# Kite-ARM-STM32F103.net
KiCad netlist of a schematic drawn in EAGLE
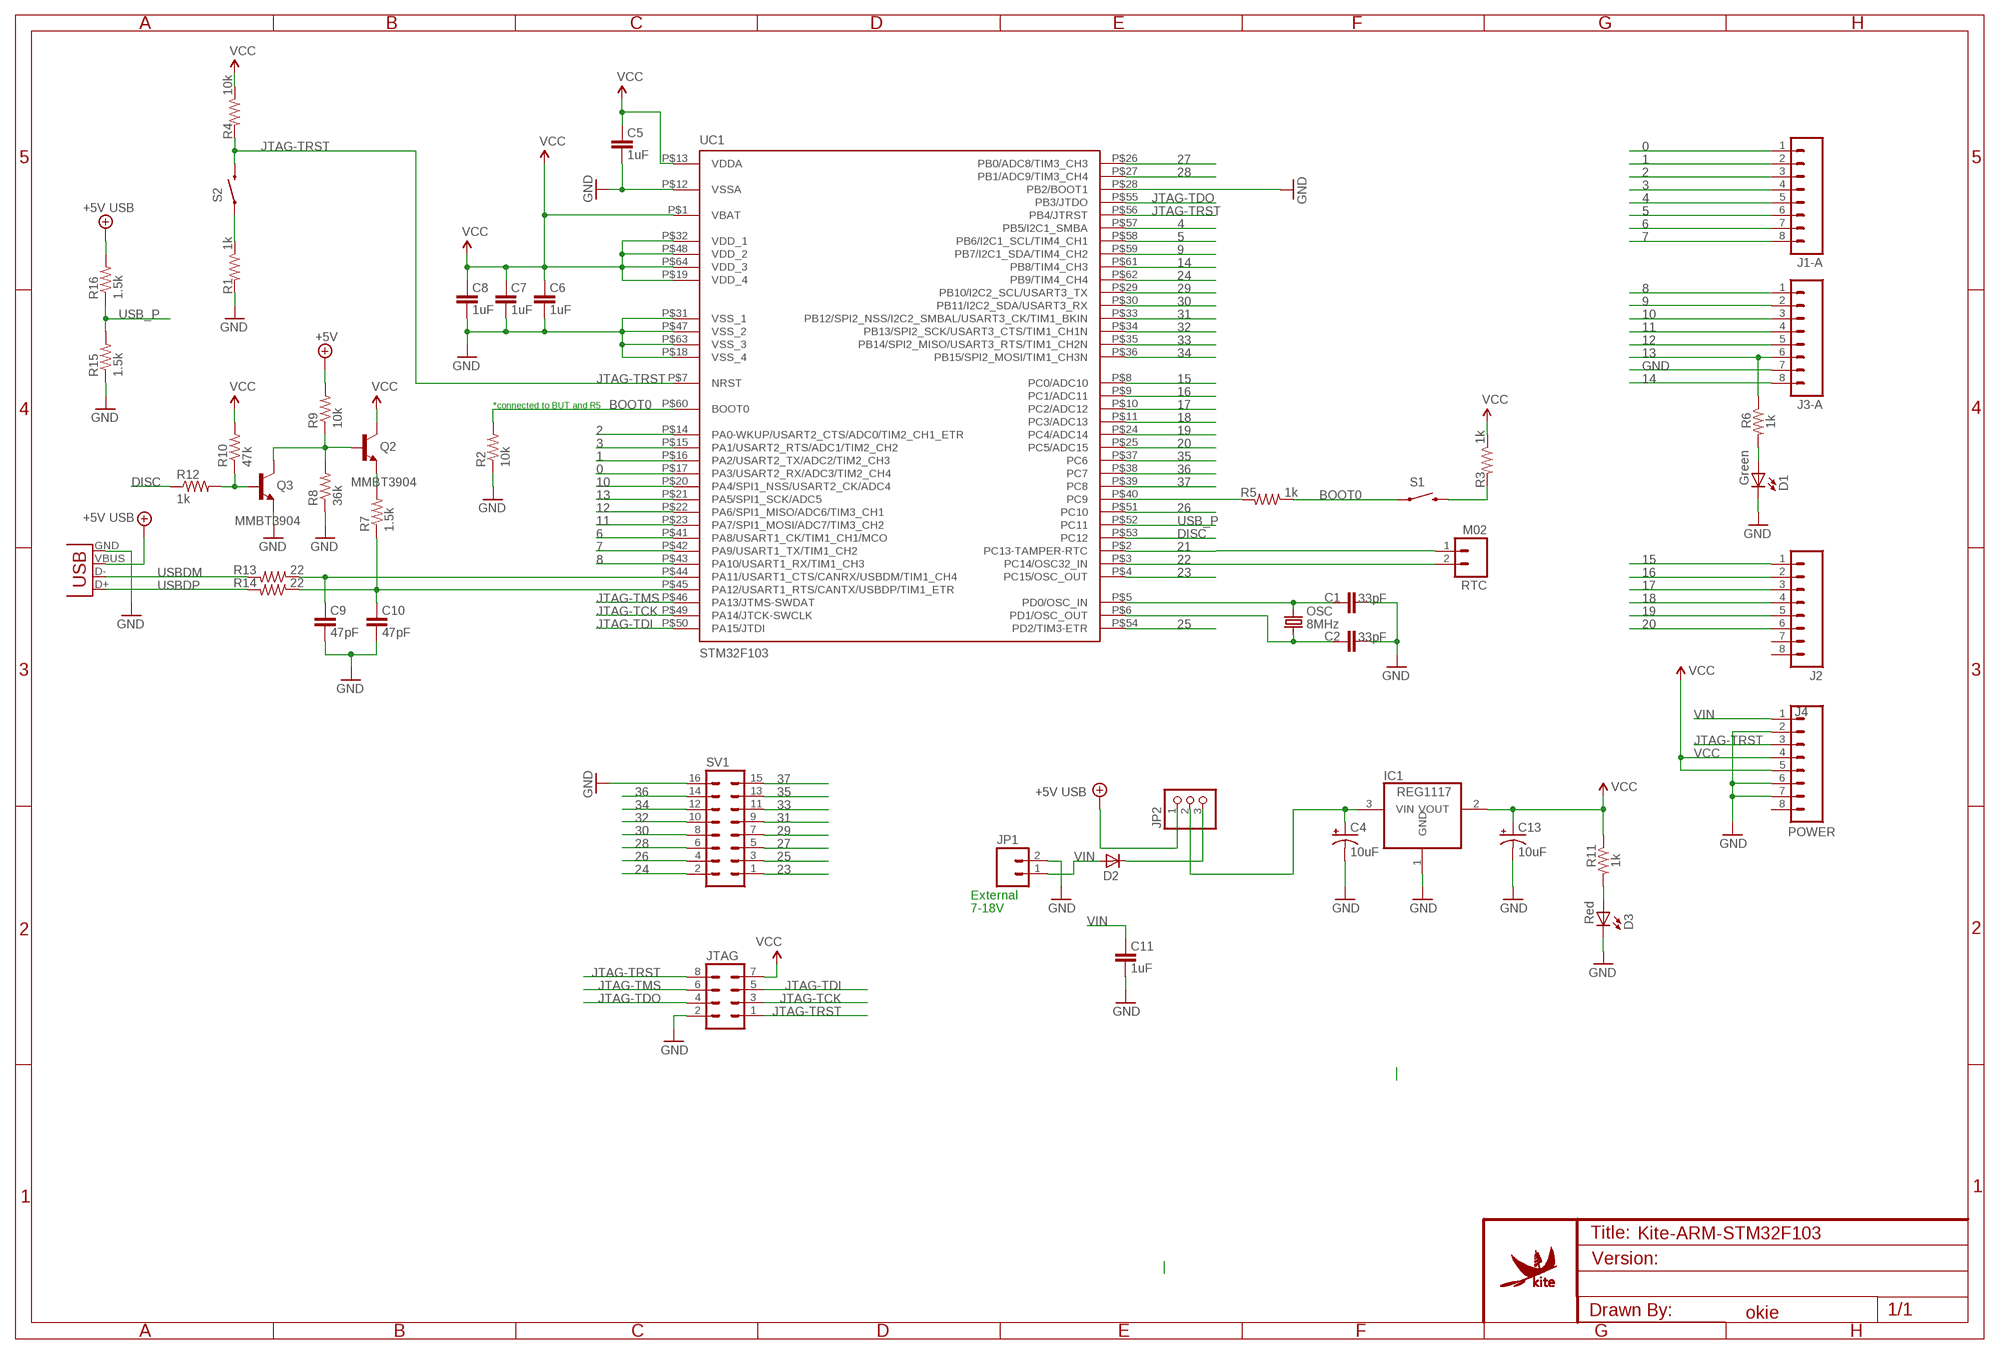
[diagram p0: schematic, sheet 1]

(export (version "E")
  (design (tool "Eeschema 10.0.6"))
  (components
    (comp (ref "C1")
      (value "33pF")
      (footprint "eagle-import:0603")
      (libsource (lib "eagle-import") (part "CAP0603"))
    )
    (comp (ref "C2")
      (value "33pF")
      (footprint "eagle-import:0603")
      (libsource (lib "eagle-import") (part "CAP0603"))
    )
    (comp (ref "C4")
      (value "10uF")
      (footprint "eagle-import:EIA3216")
      (libsource (lib "eagle-import") (part "10UF-TANT"))
    )
    (comp (ref "C5")
      (value "1uF")
      (footprint "eagle-import:0603")
      (libsource (lib "eagle-import") (part "CAP0603"))
    )
    (comp (ref "C6")
      (value "1uF")
      (footprint "eagle-import:0603")
      (libsource (lib "eagle-import") (part "CAP0603"))
    )
    (comp (ref "C7")
      (value "1uF")
      (footprint "eagle-import:0603")
      (libsource (lib "eagle-import") (part "CAP0603"))
    )
    (comp (ref "C8")
      (value "1uF")
      (footprint "eagle-import:0603")
      (libsource (lib "eagle-import") (part "CAP0603"))
    )
    (comp (ref "C9")
      (value "47pF")
      (footprint "eagle-import:0603")
      (libsource (lib "eagle-import") (part "CAP0603"))
    )
    (comp (ref "C10")
      (value "47pF")
      (footprint "eagle-import:0603")
      (libsource (lib "eagle-import") (part "CAP0603"))
    )
    (comp (ref "C11")
      (value "1uF")
      (footprint "eagle-import:0603")
      (libsource (lib "eagle-import") (part "CAP0603"))
    )
    (comp (ref "C13")
      (value "10uF")
      (footprint "eagle-import:EIA3216")
      (libsource (lib "eagle-import") (part "10UF-TANT"))
    )
    (comp (ref "D1")
      (value "Green")
      (footprint "eagle-import:LED-0603")
      (libsource (lib "eagle-import") (part "LED0603"))
    )
    (comp (ref "D2")
      (value "DIODESMA")
      (footprint "eagle-import:SMA-DIODE")
      (libsource (lib "eagle-import") (part "DIODESMA"))
    )
    (comp (ref "D3")
      (value "Red")
      (footprint "eagle-import:LED-0603")
      (libsource (lib "eagle-import") (part "LED0603"))
    )
    (comp (ref "IC1")
      (value "REG1117")
      (footprint "eagle-import:SOT223")
      (libsource (lib "eagle-import") (part "REG1117"))
    )
    (comp (ref "J1-A")
      (value "M081X08")
      (footprint "eagle-import:1X08")
      (libsource (lib "eagle-import") (part "M081X08"))
    )
    (comp (ref "J2")
      (value "M081X08")
      (footprint "eagle-import:1X08")
      (libsource (lib "eagle-import") (part "M081X08"))
    )
    (comp (ref "J3-A")
      (value "M081X08")
      (footprint "eagle-import:1X08")
      (libsource (lib "eagle-import") (part "M081X08"))
    )
    (comp (ref "J4")
      (value "POWER")
      (footprint "eagle-import:1X08")
      (libsource (lib "eagle-import") (part "M081X08"))
    )
    (comp (ref "JP1")
      (value "M02POLAR")
      (footprint "eagle-import:MOLEX-1X2")
      (libsource (lib "eagle-import") (part "M02POLAR"))
    )
    (comp (ref "JP2")
      (value "PINHD-1X3")
      (footprint "eagle-import:1X03")
      (libsource (lib "eagle-import") (part "PINHD-1X3"))
    )
    (comp (ref "JTAG")
      (value "MA04-2")
      (footprint "eagle-import:MA04-2")
      (libsource (lib "eagle-import") (part "MA04-2"))
    )
    (comp (ref "OSC")
      (value "8MHz")
      (footprint "eagle-import:CRYSTAL-SMD-5X3")
      (libsource (lib "eagle-import") (part "CRYSTAL5X3"))
    )
    (comp (ref "Q2")
      (value "MMBT3904")
      (footprint "eagle-import:SOT23")
      (libsource (lib "eagle-import") (part "TRANSISTOR_NPNSOT23"))
    )
    (comp (ref "Q3")
      (value "MMBT3904")
      (footprint "eagle-import:SOT23")
      (libsource (lib "eagle-import") (part "TRANSISTOR_NPNSOT23"))
    )
    (comp (ref "R1")
      (value "1k")
      (footprint "eagle-import:0603")
      (libsource (lib "eagle-import") (part "RESISTOR0603"))
    )
    (comp (ref "R2")
      (value "10k")
      (footprint "eagle-import:0603")
      (libsource (lib "eagle-import") (part "RESISTOR0603"))
    )
    (comp (ref "R3")
      (value "1k")
      (footprint "eagle-import:0603")
      (libsource (lib "eagle-import") (part "RESISTOR0603"))
    )
    (comp (ref "R4")
      (value "10k")
      (footprint "eagle-import:0603")
      (libsource (lib "eagle-import") (part "RESISTOR0603"))
    )
    (comp (ref "R5")
      (value "1k")
      (footprint "eagle-import:0603")
      (libsource (lib "eagle-import") (part "RESISTOR0603"))
    )
    (comp (ref "R6")
      (value "1k")
      (footprint "eagle-import:0603")
      (libsource (lib "eagle-import") (part "RESISTOR0603"))
    )
    (comp (ref "R7")
      (value "1.5k")
      (footprint "eagle-import:0603")
      (libsource (lib "eagle-import") (part "RESISTOR0603"))
    )
    (comp (ref "R8")
      (value "36k")
      (footprint "eagle-import:0603")
      (libsource (lib "eagle-import") (part "RESISTOR0603"))
    )
    (comp (ref "R9")
      (value "10k")
      (footprint "eagle-import:0603")
      (libsource (lib "eagle-import") (part "RESISTOR0603"))
    )
    (comp (ref "R10")
      (value "47k")
      (footprint "eagle-import:0603")
      (libsource (lib "eagle-import") (part "RESISTOR0603"))
    )
    (comp (ref "R11")
      (value "1k")
      (footprint "eagle-import:0603")
      (libsource (lib "eagle-import") (part "RESISTOR0603"))
    )
    (comp (ref "R12")
      (value "1k")
      (footprint "eagle-import:0603")
      (libsource (lib "eagle-import") (part "RESISTOR0603"))
    )
    (comp (ref "R13")
      (value "22")
      (footprint "eagle-import:0603")
      (libsource (lib "eagle-import") (part "RESISTOR0603"))
    )
    (comp (ref "R14")
      (value "22")
      (footprint "eagle-import:0603")
      (libsource (lib "eagle-import") (part "RESISTOR0603"))
    )
    (comp (ref "R15")
      (value "1.5k")
      (footprint "eagle-import:0603")
      (libsource (lib "eagle-import") (part "RESISTOR0603"))
    )
    (comp (ref "R16")
      (value "1.5k")
      (footprint "eagle-import:0603")
      (libsource (lib "eagle-import") (part "RESISTOR0603"))
    )
    (comp (ref "RTC")
      (value "M02")
      (footprint "eagle-import:1X02")
      (libsource (lib "eagle-import") (part "M02NG"))
    )
    (comp (ref "S1")
      (value "SWITCH-MOMENTARY-2-SMD-1101NE")
      (footprint "eagle-import:TACTILE-SWITCH-1101NE")
      (libsource (lib "eagle-import") (part "SWITCH-MOMENTARY-2-SMD-1101NE"))
    )
    (comp (ref "S2")
      (value "SWITCH-MOMENTARY-2-SMD-1101NE")
      (footprint "eagle-import:TACTILE-SWITCH-1101NE")
      (libsource (lib "eagle-import") (part "SWITCH-MOMENTARY-2-SMD-1101NE"))
    )
    (comp (ref "SV1")
      (value "MA08-2")
      (footprint "eagle-import:MA08-2")
      (libsource (lib "eagle-import") (part "MA08-2"))
    )
    (comp (ref "U$3")
      (value "KITE-LOGO-STM32-MEDIUM")
      (footprint "eagle-import:KITE-STM32-LOGO-MEDIUM")
      (libsource (lib "eagle-import") (part "KITE-LOGO-STM32-MEDIUM"))
    )
    (comp (ref "UC1")
      (value "STM32F103")
      (footprint "eagle-import:TQFP-10X10-64")
      (libsource (lib "eagle-import") (part "STM32F103"))
    )
    (comp (ref "X1")
      (value "USBSMD")
      (footprint "eagle-import:USB-MINIB")
      (libsource (lib "eagle-import") (part "USBSMD"))
    )
  )
  (nets
    (net (code "1") (name "+5V") (class "Default")
      (node (ref "JP2") (pin "1") (pinfunction "1_1") (pintype "passive"))
      (node (ref "R16") (pin "2") (pinfunction "2_2") (pintype "passive"))
      (node (ref "R9") (pin "2") (pinfunction "2_2") (pintype "passive"))
      (node (ref "X1") (pin "VBUS") (pinfunction "VBUS_VBUS") (pintype "bidirectional"))
    )
    (net (code "2") (name "/0") (class "Default")
      (node (ref "J1-A") (pin "1") (pinfunction "1_1") (pintype "passive"))
      (node (ref "UC1") (pin "P$17") (pinfunction "PA3/USART2_RX/ADC3/TIM2_CH4_P$17") (pintype "bidirectional"))
    )
    (net (code "3") (name "/1") (class "Default")
      (node (ref "J1-A") (pin "2") (pinfunction "2_2") (pintype "passive"))
      (node (ref "UC1") (pin "P$16") (pinfunction "PA2/USART2_TX/ADC2/TIM2_CH3_P$16") (pintype "bidirectional"))
    )
    (net (code "4") (name "/2") (class "Default")
      (node (ref "J1-A") (pin "3") (pinfunction "3_3") (pintype "passive"))
      (node (ref "UC1") (pin "P$14") (pinfunction "PA0-WKUP/USART2_CTS/ADC0/TIM2_CH1_ETR_P$14") (pintype "bidirectional"))
    )
    (net (code "5") (name "/3") (class "Default")
      (node (ref "J1-A") (pin "4") (pinfunction "4_4") (pintype "passive"))
      (node (ref "UC1") (pin "P$15") (pinfunction "PA1/USART2_RTS/ADC1/TIM2_CH2_P$15") (pintype "bidirectional"))
    )
    (net (code "6") (name "/4") (class "Default")
      (node (ref "J1-A") (pin "5") (pinfunction "5_5") (pintype "passive"))
      (node (ref "UC1") (pin "P$57") (pinfunction "PB5/I2C1_SMBA_P$57") (pintype "bidirectional"))
    )
    (net (code "7") (name "/5") (class "Default")
      (node (ref "J1-A") (pin "6") (pinfunction "6_6") (pintype "passive"))
      (node (ref "UC1") (pin "P$58") (pinfunction "PB6/I2C1_SCL/TIM4_CH1_P$58") (pintype "bidirectional"))
    )
    (net (code "8") (name "/6") (class "Default")
      (node (ref "J1-A") (pin "7") (pinfunction "7_7") (pintype "passive"))
      (node (ref "UC1") (pin "P$41") (pinfunction "PA8/USART1_CK/TIM1_CH1/MCO_P$41") (pintype "bidirectional"))
    )
    (net (code "9") (name "/7") (class "Default")
      (node (ref "J1-A") (pin "8") (pinfunction "8_8") (pintype "passive"))
      (node (ref "UC1") (pin "P$42") (pinfunction "PA9/USART1_TX/TIM1_CH2_P$42") (pintype "bidirectional"))
    )
    (net (code "10") (name "/8") (class "Default")
      (node (ref "J3-A") (pin "1") (pinfunction "1_1") (pintype "passive"))
      (node (ref "UC1") (pin "P$43") (pinfunction "PA10/USART1_RX/TIM1_CH3_P$43") (pintype "bidirectional"))
    )
    (net (code "11") (name "/9") (class "Default")
      (node (ref "J3-A") (pin "2") (pinfunction "2_2") (pintype "passive"))
      (node (ref "UC1") (pin "P$59") (pinfunction "PB7/I2C1_SDA/TIM4_CH2_P$59") (pintype "bidirectional"))
    )
    (net (code "12") (name "/10") (class "Default")
      (node (ref "J3-A") (pin "3") (pinfunction "3_3") (pintype "passive"))
      (node (ref "UC1") (pin "P$20") (pinfunction "PA4/SPI1_NSS/USART2_CK/ADC4_P$20") (pintype "bidirectional"))
    )
    (net (code "13") (name "/11") (class "Default")
      (node (ref "J3-A") (pin "4") (pinfunction "4_4") (pintype "passive"))
      (node (ref "UC1") (pin "P$23") (pinfunction "PA7/SPI1_MOSI/ADC7/TIM3_CH2_P$23") (pintype "bidirectional"))
    )
    (net (code "14") (name "/12") (class "Default")
      (node (ref "J3-A") (pin "5") (pinfunction "5_5") (pintype "passive"))
      (node (ref "UC1") (pin "P$22") (pinfunction "PA6/SPI1_MISO/ADC6/TIM3_CH1_P$22") (pintype "bidirectional"))
    )
    (net (code "15") (name "/13") (class "Default")
      (node (ref "J3-A") (pin "6") (pinfunction "6_6") (pintype "passive"))
      (node (ref "R6") (pin "1") (pinfunction "1_1") (pintype "passive"))
      (node (ref "UC1") (pin "P$21") (pinfunction "PA5/SPI1_SCK/ADC5_P$21") (pintype "bidirectional"))
    )
    (net (code "16") (name "/14") (class "Default")
      (node (ref "J3-A") (pin "8") (pinfunction "8_8") (pintype "passive"))
      (node (ref "UC1") (pin "P$61") (pinfunction "PB8/TIM4_CH3_P$61") (pintype "bidirectional"))
    )
    (net (code "17") (name "/15") (class "Default")
      (node (ref "J2") (pin "1") (pinfunction "1_1") (pintype "passive"))
      (node (ref "UC1") (pin "P$8") (pinfunction "PC0/ADC10_P$8") (pintype "bidirectional"))
    )
    (net (code "18") (name "/16") (class "Default")
      (node (ref "J2") (pin "2") (pinfunction "2_2") (pintype "passive"))
      (node (ref "UC1") (pin "P$9") (pinfunction "PC1/ADC11_P$9") (pintype "bidirectional"))
    )
    (net (code "19") (name "/17") (class "Default")
      (node (ref "J2") (pin "3") (pinfunction "3_3") (pintype "passive"))
      (node (ref "UC1") (pin "P$10") (pinfunction "PC2/ADC12_P$10") (pintype "bidirectional"))
    )
    (net (code "20") (name "/18") (class "Default")
      (node (ref "J2") (pin "4") (pinfunction "4_4") (pintype "passive"))
      (node (ref "UC1") (pin "P$11") (pinfunction "PC3/ADC13_P$11") (pintype "bidirectional"))
    )
    (net (code "21") (name "/19") (class "Default")
      (node (ref "J2") (pin "5") (pinfunction "5_5") (pintype "passive"))
      (node (ref "UC1") (pin "P$24") (pinfunction "PC4/ADC14_P$24") (pintype "bidirectional"))
    )
    (net (code "22") (name "/20") (class "Default")
      (node (ref "J2") (pin "6") (pinfunction "6_6") (pintype "passive"))
      (node (ref "UC1") (pin "P$25") (pinfunction "PC5/ADC15_P$25") (pintype "bidirectional"))
    )
    (net (code "23") (name "/21") (class "Default")
      (node (ref "RTC") (pin "1") (pinfunction "1_1") (pintype "passive"))
      (node (ref "UC1") (pin "P$2") (pinfunction "PC13-TAMPER-RTC_P$2") (pintype "bidirectional"))
    )
    (net (code "24") (name "/22") (class "Default")
      (node (ref "RTC") (pin "2") (pinfunction "2_2") (pintype "passive"))
      (node (ref "UC1") (pin "P$3") (pinfunction "PC14/OSC32_IN_P$3") (pintype "bidirectional"))
    )
    (net (code "25") (name "/23") (class "Default")
      (node (ref "SV1") (pin "1") (pinfunction "1_1") (pintype "passive"))
      (node (ref "UC1") (pin "P$4") (pinfunction "PC15/OSC_OUT_P$4") (pintype "bidirectional"))
    )
    (net (code "26") (name "/24") (class "Default")
      (node (ref "SV1") (pin "2") (pinfunction "2_2") (pintype "passive"))
      (node (ref "UC1") (pin "P$62") (pinfunction "PB9/TIM4_CH4_P$62") (pintype "bidirectional"))
    )
    (net (code "27") (name "/25") (class "Default")
      (node (ref "SV1") (pin "3") (pinfunction "3_3") (pintype "passive"))
      (node (ref "UC1") (pin "P$54") (pinfunction "PD2/TIM3-ETR_P$54") (pintype "bidirectional"))
    )
    (net (code "28") (name "/26") (class "Default")
      (node (ref "SV1") (pin "4") (pinfunction "4_4") (pintype "passive"))
      (node (ref "UC1") (pin "P$51") (pinfunction "PC10_P$51") (pintype "bidirectional"))
    )
    (net (code "29") (name "/27") (class "Default")
      (node (ref "SV1") (pin "5") (pinfunction "5_5") (pintype "passive"))
      (node (ref "UC1") (pin "P$26") (pinfunction "PB0/ADC8/TIM3_CH3_P$26") (pintype "bidirectional"))
    )
    (net (code "30") (name "/28") (class "Default")
      (node (ref "SV1") (pin "6") (pinfunction "6_6") (pintype "passive"))
      (node (ref "UC1") (pin "P$27") (pinfunction "PB1/ADC9/TIM3_CH4_P$27") (pintype "bidirectional"))
    )
    (net (code "31") (name "/29") (class "Default")
      (node (ref "SV1") (pin "7") (pinfunction "7_7") (pintype "passive"))
      (node (ref "UC1") (pin "P$29") (pinfunction "PB10/I2C2_SCL/USART3_TX_P$29") (pintype "bidirectional"))
    )
    (net (code "32") (name "/30") (class "Default")
      (node (ref "SV1") (pin "8") (pinfunction "8_8") (pintype "passive"))
      (node (ref "UC1") (pin "P$30") (pinfunction "PB11/I2C2_SDA/USART3_RX_P$30") (pintype "bidirectional"))
    )
    (net (code "33") (name "/31") (class "Default")
      (node (ref "SV1") (pin "9") (pinfunction "9_9") (pintype "passive"))
      (node (ref "UC1") (pin "P$33") (pinfunction "PB12/SPI2_NSS/I2C2_SMBAL/USART3_CK/TIM1_BKIN_P$33") (pintype "bidirectional"))
    )
    (net (code "34") (name "/32") (class "Default")
      (node (ref "SV1") (pin "10") (pinfunction "10_10") (pintype "passive"))
      (node (ref "UC1") (pin "P$34") (pinfunction "PB13/SPI2_SCK/USART3_CTS/TIM1_CH1N_P$34") (pintype "bidirectional"))
    )
    (net (code "35") (name "/33") (class "Default")
      (node (ref "SV1") (pin "11") (pinfunction "11_11") (pintype "passive"))
      (node (ref "UC1") (pin "P$35") (pinfunction "PB14/SPI2_MISO/USART3_RTS/TIM1_CH2N_P$35") (pintype "bidirectional"))
    )
    (net (code "36") (name "/34") (class "Default")
      (node (ref "SV1") (pin "12") (pinfunction "12_12") (pintype "passive"))
      (node (ref "UC1") (pin "P$36") (pinfunction "PB15/SPI2_MOSI/TIM1_CH3N_P$36") (pintype "bidirectional"))
    )
    (net (code "37") (name "/35") (class "Default")
      (node (ref "SV1") (pin "13") (pinfunction "13_13") (pintype "passive"))
      (node (ref "UC1") (pin "P$37") (pinfunction "PC6_P$37") (pintype "bidirectional"))
    )
    (net (code "38") (name "/36") (class "Default")
      (node (ref "SV1") (pin "14") (pinfunction "14_14") (pintype "passive"))
      (node (ref "UC1") (pin "P$38") (pinfunction "PC7_P$38") (pintype "bidirectional"))
    )
    (net (code "39") (name "/37") (class "Default")
      (node (ref "SV1") (pin "15") (pinfunction "15_15") (pintype "passive"))
      (node (ref "UC1") (pin "P$39") (pinfunction "PC8_P$39") (pintype "bidirectional"))
    )
    (net (code "40") (name "/BOOT0") (class "Default")
      (node (ref "R2") (pin "2") (pinfunction "2_2") (pintype "passive"))
      (node (ref "R5") (pin "1") (pinfunction "1_1") (pintype "passive"))
      (node (ref "S1") (pin "P$1") (pinfunction "1_P$1") (pintype "passive"))
      (node (ref "UC1") (pin "P$60") (pinfunction "BOOT0_P$60") (pintype "bidirectional"))
    )
    (net (code "41") (name "/DISC") (class "Default")
      (node (ref "R12") (pin "1") (pinfunction "1_1") (pintype "passive"))
      (node (ref "UC1") (pin "P$53") (pinfunction "PC12_P$53") (pintype "bidirectional"))
    )
    (net (code "42") (name "/JTAG-TCK") (class "Default")
      (node (ref "JTAG") (pin "3") (pinfunction "3_3") (pintype "passive"))
      (node (ref "UC1") (pin "P$49") (pinfunction "PA14/JTCK-SWCLK_P$49") (pintype "bidirectional"))
    )
    (net (code "43") (name "/JTAG-TDI") (class "Default")
      (node (ref "JTAG") (pin "5") (pinfunction "5_5") (pintype "passive"))
      (node (ref "UC1") (pin "P$50") (pinfunction "PA15/JTDI_P$50") (pintype "bidirectional"))
    )
    (net (code "44") (name "/JTAG-TDO") (class "Default")
      (node (ref "JTAG") (pin "4") (pinfunction "4_4") (pintype "passive"))
      (node (ref "UC1") (pin "P$55") (pinfunction "PB3/JTDO_P$55") (pintype "bidirectional"))
    )
    (net (code "45") (name "/JTAG-TMS") (class "Default")
      (node (ref "JTAG") (pin "6") (pinfunction "6_6") (pintype "passive"))
      (node (ref "UC1") (pin "P$46") (pinfunction "PA13/JTMS-SWDAT_P$46") (pintype "bidirectional"))
    )
    (net (code "46") (name "/JTAG-TRST") (class "Default")
      (node (ref "J4") (pin "3") (pinfunction "3_3") (pintype "passive"))
      (node (ref "JTAG") (pin "1") (pinfunction "1_1") (pintype "passive"))
      (node (ref "JTAG") (pin "8") (pinfunction "8_8") (pintype "passive"))
      (node (ref "R4") (pin "2") (pinfunction "2_2") (pintype "passive"))
      (node (ref "S2") (pin "P$2") (pinfunction "2_P$2") (pintype "passive"))
      (node (ref "UC1") (pin "P$56") (pinfunction "PB4/JTRST_P$56") (pintype "bidirectional"))
      (node (ref "UC1") (pin "P$7") (pinfunction "NRST_P$7") (pintype "bidirectional"))
    )
    (net (code "47") (name "/USBDM") (class "Default")
      (node (ref "R13") (pin "2") (pinfunction "2_2") (pintype "passive"))
      (node (ref "X1") (pin "D-") (pinfunction "D-_D-") (pintype "bidirectional"))
    )
    (net (code "48") (name "/USBDP") (class "Default")
      (node (ref "R14") (pin "2") (pinfunction "2_2") (pintype "passive"))
      (node (ref "X1") (pin "D+") (pinfunction "D+_D+") (pintype "bidirectional"))
    )
    (net (code "49") (name "/USB_P") (class "Default")
      (node (ref "R15") (pin "2") (pinfunction "2_2") (pintype "passive"))
      (node (ref "R16") (pin "1") (pinfunction "1_1") (pintype "passive"))
      (node (ref "UC1") (pin "P$52") (pinfunction "PC11_P$52") (pintype "bidirectional"))
    )
    (net (code "50") (name "/VIN") (class "Default")
      (node (ref "C11") (pin "2") (pinfunction "2_2") (pintype "passive"))
      (node (ref "D2") (pin "A") (pinfunction "A_A") (pintype "passive"))
      (node (ref "J4") (pin "1") (pinfunction "1_1") (pintype "passive"))
      (node (ref "JP1") (pin "1") (pinfunction "1_1") (pintype "passive"))
    )
    (net (code "51") (name "GND") (class "Default")
      (node (ref "C1") (pin "1") (pinfunction "1_1") (pintype "passive"))
      (node (ref "C10") (pin "1") (pinfunction "1_1") (pintype "passive"))
      (node (ref "C11") (pin "1") (pinfunction "1_1") (pintype "passive"))
      (node (ref "C13") (pin "C") (pinfunction "-_C") (pintype "passive"))
      (node (ref "C2") (pin "1") (pinfunction "1_1") (pintype "passive"))
      (node (ref "C4") (pin "C") (pinfunction "-_C") (pintype "passive"))
      (node (ref "C5") (pin "1") (pinfunction "1_1") (pintype "passive"))
      (node (ref "C6") (pin "1") (pinfunction "1_1") (pintype "passive"))
      (node (ref "C7") (pin "1") (pinfunction "1_1") (pintype "passive"))
      (node (ref "C8") (pin "1") (pinfunction "1_1") (pintype "passive"))
      (node (ref "C9") (pin "1") (pinfunction "1_1") (pintype "passive"))
      (node (ref "D1") (pin "C") (pinfunction "C_C") (pintype "passive"))
      (node (ref "D3") (pin "C") (pinfunction "C_C") (pintype "passive"))
      (node (ref "IC1") (pin "1") (pinfunction "GND_1") (pintype "power_in"))
      (node (ref "J3-A") (pin "7") (pinfunction "7_7") (pintype "passive"))
      (node (ref "J4") (pin "2") (pinfunction "2_2") (pintype "passive"))
      (node (ref "J4") (pin "6") (pinfunction "6_6") (pintype "passive"))
      (node (ref "J4") (pin "7") (pinfunction "7_7") (pintype "passive"))
      (node (ref "JP1") (pin "2") (pinfunction "2_2") (pintype "passive"))
      (node (ref "JTAG") (pin "2") (pinfunction "2_2") (pintype "passive"))
      (node (ref "Q3") (pin "2") (pinfunction "E_2") (pintype "passive"))
      (node (ref "R1") (pin "2") (pinfunction "2_2") (pintype "passive"))
      (node (ref "R15") (pin "1") (pinfunction "1_1") (pintype "passive"))
      (node (ref "R2") (pin "1") (pinfunction "1_1") (pintype "passive"))
      (node (ref "R8") (pin "1") (pinfunction "1_1") (pintype "passive"))
      (node (ref "SV1") (pin "16") (pinfunction "16_16") (pintype "passive"))
      (node (ref "UC1") (pin "P$12") (pinfunction "VSSA_P$12") (pintype "power_in"))
      (node (ref "UC1") (pin "P$18") (pinfunction "VSS_4_P$18") (pintype "power_in"))
      (node (ref "UC1") (pin "P$28") (pinfunction "PB2/BOOT1_P$28") (pintype "bidirectional"))
      (node (ref "UC1") (pin "P$31") (pinfunction "VSS_1_P$31") (pintype "power_in"))
      (node (ref "UC1") (pin "P$47") (pinfunction "VSS_2_P$47") (pintype "power_in"))
      (node (ref "UC1") (pin "P$63") (pinfunction "VSS_3_P$63") (pintype "power_in"))
      (node (ref "X1") (pin "GND") (pinfunction "GND_GND") (pintype "bidirectional"))
    )
    (net (code "52") (name "Net-(C4-+)") (class "Default")
      (node (ref "C4") (pin "A") (pinfunction "+_A") (pintype "passive"))
      (node (ref "IC1") (pin "3") (pinfunction "VIN_3") (pintype "input"))
      (node (ref "JP2") (pin "2") (pinfunction "2_2") (pintype "passive"))
    )
    (net (code "53") (name "Net-(D1-PadA)") (class "Default")
      (node (ref "D1") (pin "A") (pinfunction "A_A") (pintype "passive"))
      (node (ref "R6") (pin "2") (pinfunction "2_2") (pintype "passive"))
    )
    (net (code "54") (name "Net-(D2-PadC)") (class "Default")
      (node (ref "D2") (pin "C") (pinfunction "C_C") (pintype "passive"))
      (node (ref "JP2") (pin "3") (pinfunction "3_3") (pintype "passive"))
    )
    (net (code "55") (name "Net-(D3-PadA)") (class "Default")
      (node (ref "D3") (pin "A") (pinfunction "A_A") (pintype "passive"))
      (node (ref "R11") (pin "2") (pinfunction "2_2") (pintype "passive"))
    )
    (net (code "56") (name "Net-(OSC-2)") (class "Default")
      (node (ref "C1") (pin "2") (pinfunction "2_2") (pintype "passive"))
      (node (ref "OSC") (pin "3") (pinfunction "2_3") (pintype "passive"))
      (node (ref "UC1") (pin "P$5") (pinfunction "PD0/OSC_IN_P$5") (pintype "bidirectional"))
    )
    (net (code "57") (name "Net-(Q2-B)") (class "Default")
      (node (ref "Q2") (pin "1") (pinfunction "B_1") (pintype "passive"))
      (node (ref "Q3") (pin "3") (pinfunction "C_3") (pintype "passive"))
      (node (ref "R8") (pin "2") (pinfunction "2_2") (pintype "passive"))
      (node (ref "R9") (pin "1") (pinfunction "1_1") (pintype "passive"))
    )
    (net (code "58") (name "Net-(Q2-E)") (class "Default")
      (node (ref "Q2") (pin "2") (pinfunction "E_2") (pintype "passive"))
      (node (ref "R7") (pin "2") (pinfunction "2_2") (pintype "passive"))
    )
    (net (code "59") (name "Net-(Q3-B)") (class "Default")
      (node (ref "Q3") (pin "1") (pinfunction "B_1") (pintype "passive"))
      (node (ref "R10") (pin "1") (pinfunction "1_1") (pintype "passive"))
      (node (ref "R12") (pin "2") (pinfunction "2_2") (pintype "passive"))
    )
    (net (code "60") (name "Net-(S1-2)") (class "Default")
      (node (ref "R3") (pin "2") (pinfunction "2_2") (pintype "passive"))
      (node (ref "S1") (pin "P$2") (pinfunction "2_P$2") (pintype "passive"))
    )
    (net (code "61") (name "Net-(S2-1)") (class "Default")
      (node (ref "R1") (pin "1") (pinfunction "1_1") (pintype "passive"))
      (node (ref "S2") (pin "P$1") (pinfunction "1_P$1") (pintype "passive"))
    )
    (net (code "62") (name "Net-(UC1-PA11{slash}USART1_CTS{slash}CANRX{slash}USBDM{slash}TIM1_CH4)") (class "Default")
      (node (ref "C9") (pin "2") (pinfunction "2_2") (pintype "passive"))
      (node (ref "R13") (pin "1") (pinfunction "1_1") (pintype "passive"))
      (node (ref "UC1") (pin "P$44") (pinfunction "PA11/USART1_CTS/CANRX/USBDM/TIM1_CH4_P$44") (pintype "bidirectional"))
    )
    (net (code "63") (name "Net-(UC1-PA12{slash}USART1_RTS{slash}CANTX{slash}USBDP{slash}TIM1_ETR)") (class "Default")
      (node (ref "C10") (pin "2") (pinfunction "2_2") (pintype "passive"))
      (node (ref "R14") (pin "1") (pinfunction "1_1") (pintype "passive"))
      (node (ref "R7") (pin "1") (pinfunction "1_1") (pintype "passive"))
      (node (ref "UC1") (pin "P$45") (pinfunction "PA12/USART1_RTS/CANTX/USBDP/TIM1_ETR_P$45") (pintype "bidirectional"))
    )
    (net (code "64") (name "Net-(UC1-PC9)") (class "Default")
      (node (ref "R5") (pin "2") (pinfunction "2_2") (pintype "passive"))
      (node (ref "UC1") (pin "P$40") (pinfunction "PC9_P$40") (pintype "bidirectional"))
    )
    (net (code "65") (name "Net-(UC1-PD1{slash}OSC_OUT)") (class "Default")
      (node (ref "C2") (pin "2") (pinfunction "2_2") (pintype "passive"))
      (node (ref "OSC") (pin "1") (pinfunction "1_1") (pintype "passive"))
      (node (ref "UC1") (pin "P$6") (pinfunction "PD1/OSC_OUT_P$6") (pintype "bidirectional"))
    )
    (net (code "66") (name "VCC") (class "Default")
      (node (ref "C13") (pin "A") (pinfunction "+_A") (pintype "passive"))
      (node (ref "C5") (pin "2") (pinfunction "2_2") (pintype "passive"))
      (node (ref "C6") (pin "2") (pinfunction "2_2") (pintype "passive"))
      (node (ref "C7") (pin "2") (pinfunction "2_2") (pintype "passive"))
      (node (ref "C8") (pin "2") (pinfunction "2_2") (pintype "passive"))
      (node (ref "IC1") (pin "2") (pinfunction "VOUT_2") (pintype "output"))
      (node (ref "J4") (pin "4") (pinfunction "4_4") (pintype "passive"))
      (node (ref "J4") (pin "5") (pinfunction "5_5") (pintype "passive"))
      (node (ref "JTAG") (pin "7") (pinfunction "7_7") (pintype "passive"))
      (node (ref "Q2") (pin "3") (pinfunction "C_3") (pintype "passive"))
      (node (ref "R10") (pin "2") (pinfunction "2_2") (pintype "passive"))
      (node (ref "R11") (pin "1") (pinfunction "1_1") (pintype "passive"))
      (node (ref "R3") (pin "1") (pinfunction "1_1") (pintype "passive"))
      (node (ref "R4") (pin "1") (pinfunction "1_1") (pintype "passive"))
      (node (ref "UC1") (pin "P$1") (pinfunction "VBAT_P$1") (pintype "power_in"))
      (node (ref "UC1") (pin "P$13") (pinfunction "VDDA_P$13") (pintype "power_in"))
      (node (ref "UC1") (pin "P$19") (pinfunction "VDD_4_P$19") (pintype "power_in"))
      (node (ref "UC1") (pin "P$32") (pinfunction "VDD_1_P$32") (pintype "power_in"))
      (node (ref "UC1") (pin "P$48") (pinfunction "VDD_2_P$48") (pintype "power_in"))
      (node (ref "UC1") (pin "P$64") (pinfunction "VDD_3_P$64") (pintype "power_in"))
    )
    (net (code "67") (name "unconnected-(J2-Pad7)") (class "Default")
      (node (ref "J2") (pin "7") (pinfunction "7_7") (pintype "passive"))
    )
    (net (code "68") (name "unconnected-(J2-Pad8)") (class "Default")
      (node (ref "J2") (pin "8") (pinfunction "8_8") (pintype "passive"))
    )
    (net (code "69") (name "unconnected-(J4-Pad8)") (class "Default")
      (node (ref "J4") (pin "8") (pinfunction "8_8") (pintype "passive"))
    )
  )
)
